# MYBOARD_03-CORE_SRAM.net
KiCad netlist of a schematic drawn in Altium Designer
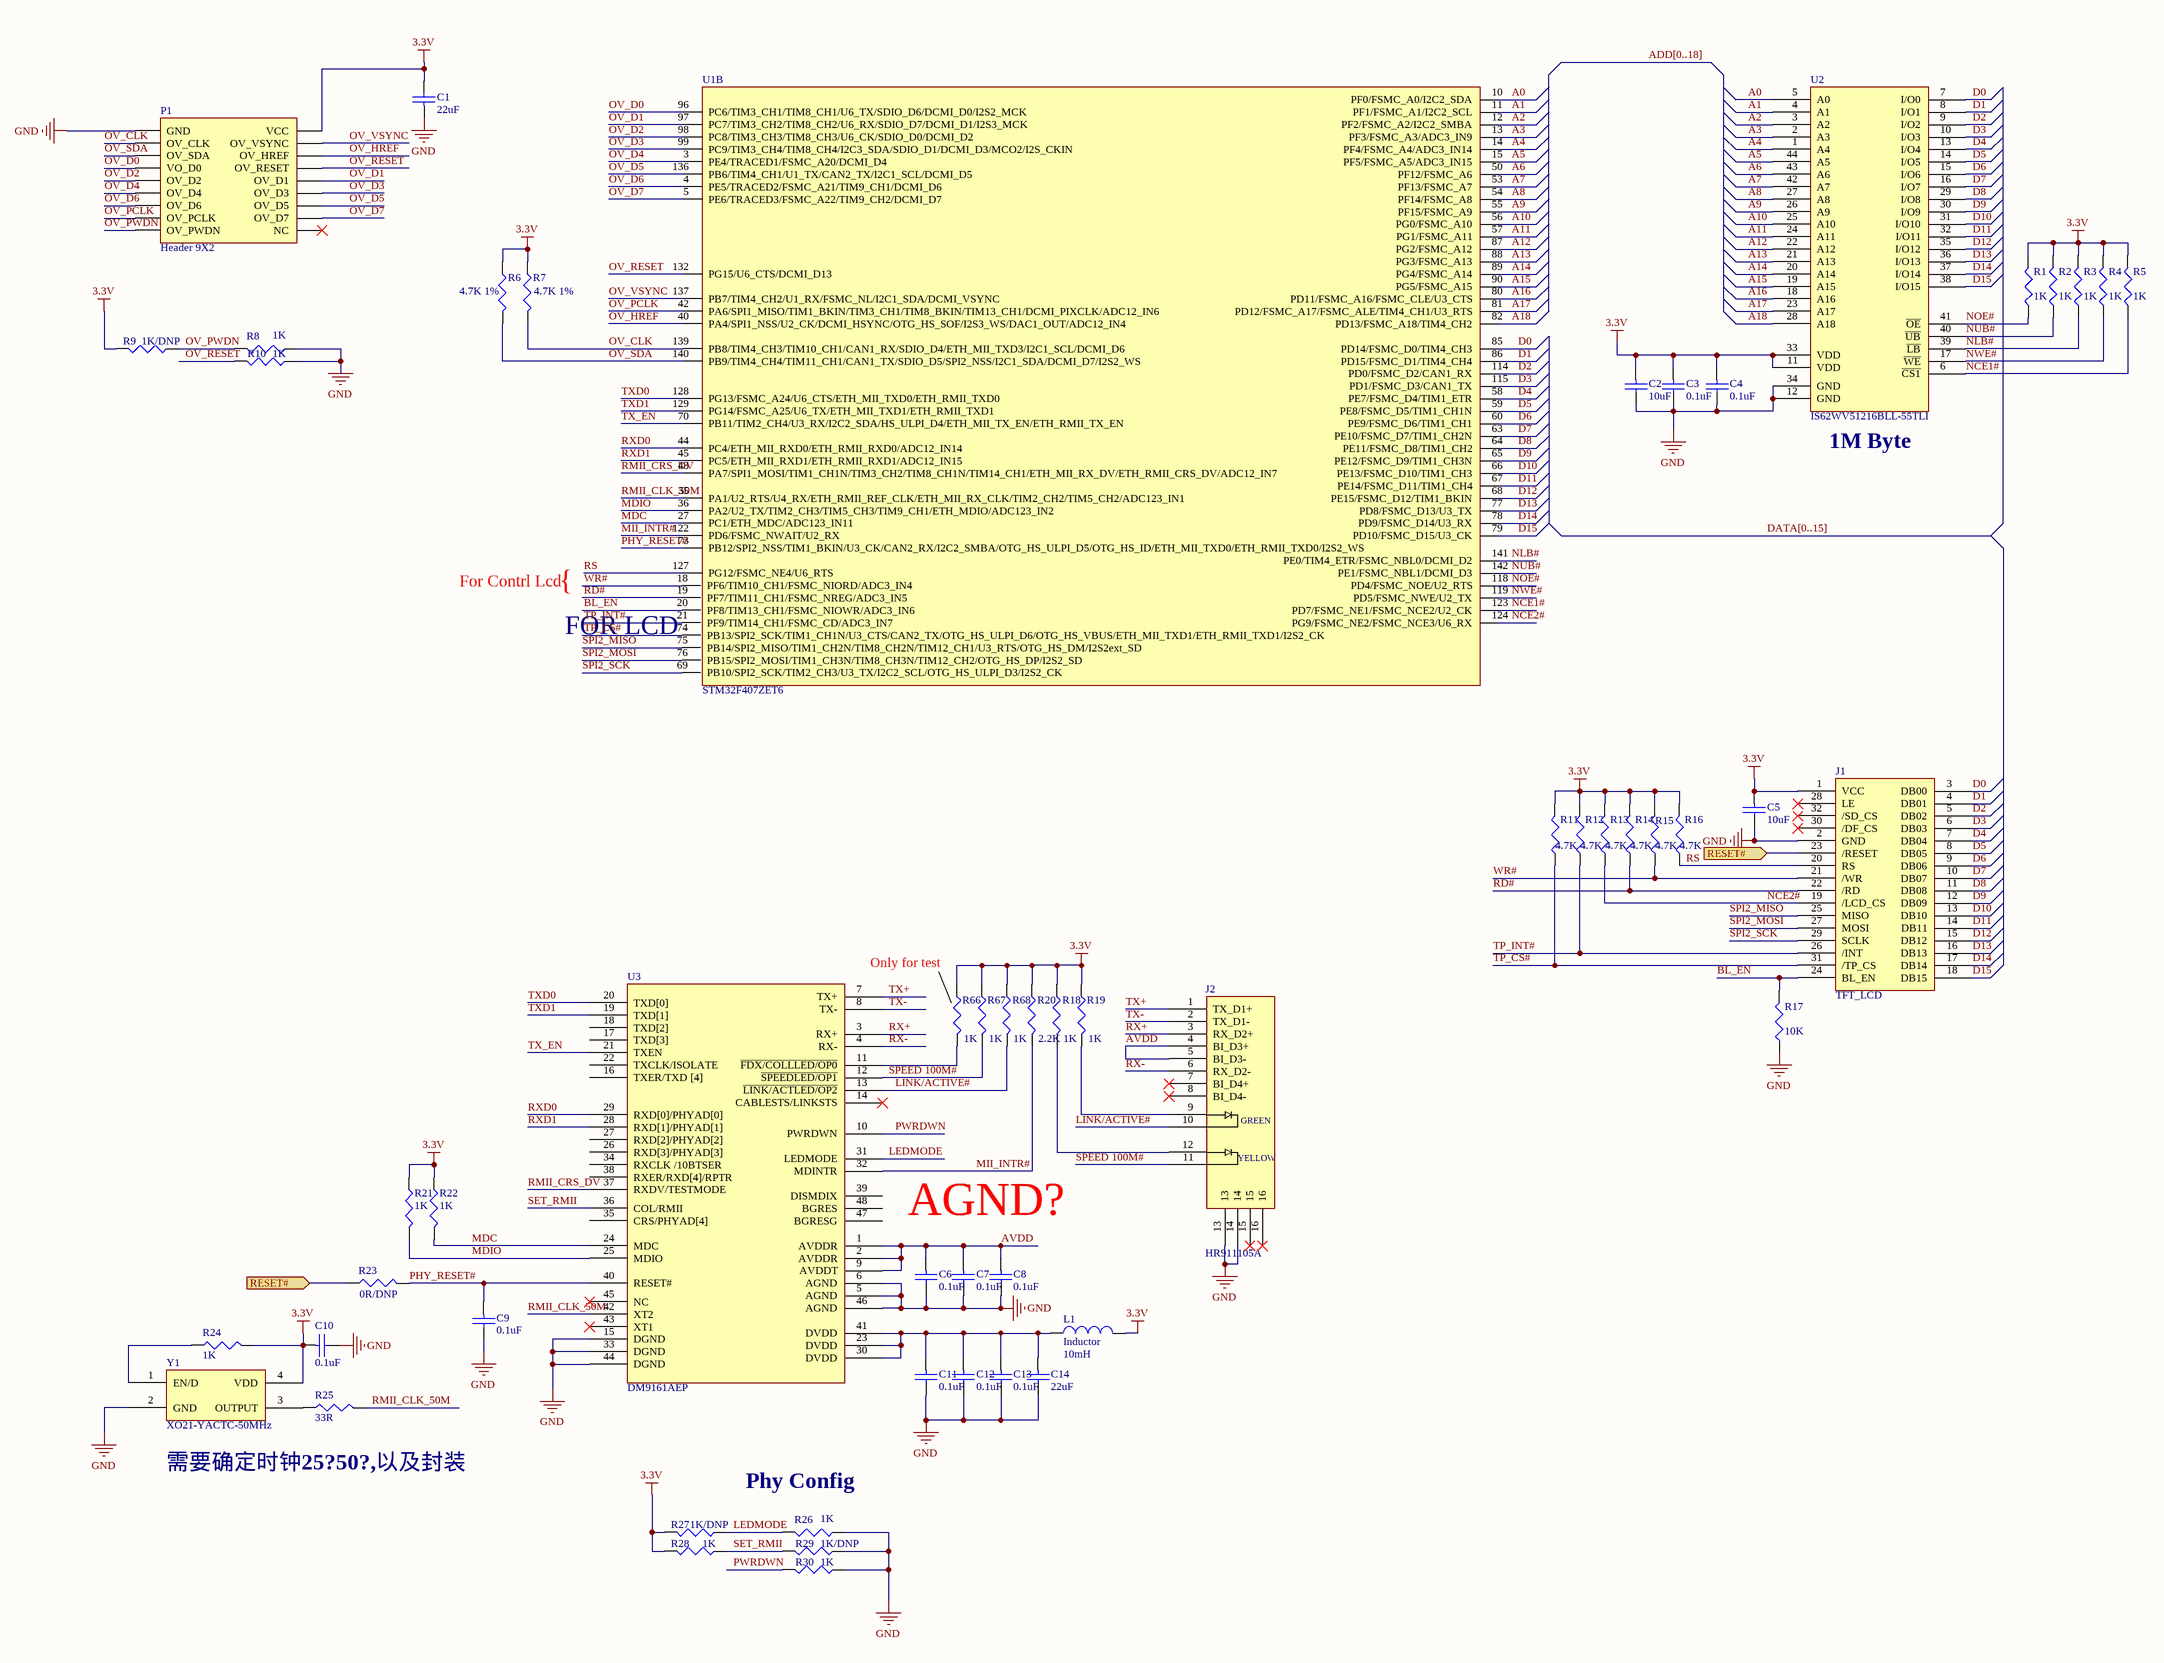
[diagram p0: MYBOARD_03-CORE&SRAM.SchDoc]

(export (version "E")
  (design (tool "Eeschema 10.0.6"))
  (components
    (comp (ref "C1")
      (value "22uF")
      (footprint "C1206")
      (description "Capacitor")
      (libsource (lib "ortho fixture") (part "CAP"))
    )
    (comp (ref "C2")
      (value "10uF")
      (footprint "C0603_DWS")
      (description "Capacitor")
      (libsource (lib "ortho fixture") (part "CAP"))
    )
    (comp (ref "C3")
      (value "0.1uF")
      (footprint "C0603_DWS")
      (description "Capacitor")
      (libsource (lib "ortho fixture") (part "CAP"))
    )
    (comp (ref "C4")
      (value "0.1uF")
      (footprint "C0603_DWS")
      (description "Capacitor")
      (libsource (lib "ortho fixture") (part "CAP"))
    )
    (comp (ref "C5")
      (value "10uF")
      (footprint "C0603_DWS")
      (description "Capacitor")
      (libsource (lib "ortho fixture") (part "CAP"))
    )
    (comp (ref "C6")
      (value "0.1uF")
      (footprint "C0603_DWS")
      (description "Capacitor")
      (libsource (lib "ortho fixture") (part "CAP"))
    )
    (comp (ref "C7")
      (value "0.1uF")
      (footprint "C0603_DWS")
      (description "Capacitor")
      (libsource (lib "ortho fixture") (part "CAP"))
    )
    (comp (ref "C8")
      (value "0.1uF")
      (footprint "C0603_DWS")
      (description "Capacitor")
      (libsource (lib "ortho fixture") (part "CAP"))
    )
    (comp (ref "C9")
      (value "0.1uF")
      (footprint "C0603_DWS")
      (description "Capacitor")
      (libsource (lib "ortho fixture") (part "CAP"))
    )
    (comp (ref "C10")
      (value "0.1uF")
      (footprint "C0603_DWS")
      (description "Capacitor")
      (libsource (lib "ortho fixture") (part "CAP"))
    )
    (comp (ref "C11")
      (value "0.1uF")
      (footprint "C0603_DWS")
      (description "Capacitor")
      (libsource (lib "ortho fixture") (part "CAP"))
    )
    (comp (ref "C12")
      (value "0.1uF")
      (footprint "C0603_DWS")
      (description "Capacitor")
      (libsource (lib "ortho fixture") (part "CAP"))
    )
    (comp (ref "C13")
      (value "0.1uF")
      (footprint "C0603_DWS")
      (description "Capacitor")
      (libsource (lib "ortho fixture") (part "CAP"))
    )
    (comp (ref "C14")
      (value "22uF")
      (footprint "C1206")
      (description "Capacitor")
      (libsource (lib "ortho fixture") (part "CAP"))
    )
    (comp (ref "J1")
      (value "TFT_LCD")
      (footprint "TFT LCD")
      (description "320x240,32PIN,")
      (libsource (lib "ortho fixture") (part "TFT_LCD"))
    )
    (comp (ref "J2")
      (value "HR911105A")
      (footprint "HR911105A")
      (libsource (lib "ortho fixture") (part "RJ45,10/100 Base -TX,有变压器"))
    )
    (comp (ref "L1")
      (value "Inductor")
      (footprint "0603")
      (fields (field (name "ALTIUM_VALUE") "10mH") (field (name "PUBLISHER") "Altium Limited"))
      (libsource (lib "Miscellaneous Devices") (part "Inductor"))
    )
    (comp (ref "P1")
      (value "Header 9X2")
      (footprint "HDR2X9")
      (description "Header, 9-Pin, Dual row")
      (fields (field (name "PUBLISHER") "Altium Limited"))
      (libsource (lib "ortho fixture") (part "Header 9X2"))
    )
    (comp (ref "R1")
      (value "1K")
      (footprint "R0603_5MIL_DWS")
      (description "Resistor")
      (fields (field (name "Comment") "Res3") (field (name "PUBLISHER") "Altium Limited"))
      (libsource (lib "Miscellaneous Devices") (part "Res3"))
    )
    (comp (ref "R2")
      (value "1K")
      (footprint "R0603_5MIL_DWS")
      (description "Resistor")
      (fields (field (name "Comment") "Res3") (field (name "PUBLISHER") "Altium Limited"))
      (libsource (lib "Miscellaneous Devices") (part "Res3"))
    )
    (comp (ref "R3")
      (value "1K")
      (footprint "R0603_5MIL_DWS")
      (description "Resistor")
      (fields (field (name "Comment") "Res3") (field (name "PUBLISHER") "Altium Limited"))
      (libsource (lib "Miscellaneous Devices") (part "Res3"))
    )
    (comp (ref "R4")
      (value "1K")
      (footprint "R0603_5MIL_DWS")
      (description "Resistor")
      (fields (field (name "Comment") "Res3") (field (name "PUBLISHER") "Altium Limited"))
      (libsource (lib "Miscellaneous Devices") (part "Res3"))
    )
    (comp (ref "R5")
      (value "1K")
      (footprint "R0603_5MIL_DWS")
      (description "Resistor")
      (fields (field (name "Comment") "Res3") (field (name "PUBLISHER") "Altium Limited"))
      (libsource (lib "Miscellaneous Devices") (part "Res3"))
    )
    (comp (ref "R6")
      (value "4.7K 1%")
      (footprint "R0603_5MIL_DWS")
      (description "Resistor")
      (fields (field (name "Comment") "Res3") (field (name "PUBLISHER") "Altium Limited"))
      (libsource (lib "Miscellaneous Devices") (part "Res3"))
    )
    (comp (ref "R7")
      (value "4.7K 1%")
      (footprint "R0603_5MIL_DWS")
      (description "Resistor")
      (fields (field (name "Comment") "Res3") (field (name "PUBLISHER") "Altium Limited"))
      (libsource (lib "Miscellaneous Devices") (part "Res3"))
    )
    (comp (ref "R8")
      (value "1K")
      (footprint "R0603_5MIL_DWS")
      (description "Resistor")
      (fields (field (name "Comment") "Res3") (field (name "PUBLISHER") "Altium Limited"))
      (libsource (lib "Miscellaneous Devices") (part "Res3"))
    )
    (comp (ref "R9")
      (value "1K/DNP")
      (footprint "R0603_5MIL_DWS")
      (description "Resistor")
      (fields (field (name "Comment") "Res3") (field (name "PUBLISHER") "Altium Limited"))
      (libsource (lib "Miscellaneous Devices") (part "Res3"))
    )
    (comp (ref "R10")
      (value "1K")
      (footprint "R0603_5MIL_DWS")
      (description "Resistor")
      (fields (field (name "Comment") "Res3") (field (name "PUBLISHER") "Altium Limited"))
      (libsource (lib "Miscellaneous Devices") (part "Res3"))
    )
    (comp (ref "R11")
      (value "4.7K")
      (footprint "R0603_5MIL_DWS")
      (description "Resistor")
      (fields (field (name "Comment") "Res3") (field (name "PUBLISHER") "Altium Limited"))
      (libsource (lib "Miscellaneous Devices") (part "Res3"))
    )
    (comp (ref "R12")
      (value "4.7K")
      (footprint "R0603_5MIL_DWS")
      (description "Resistor")
      (fields (field (name "Comment") "Res3") (field (name "PUBLISHER") "Altium Limited"))
      (libsource (lib "Miscellaneous Devices") (part "Res3"))
    )
    (comp (ref "R13")
      (value "4.7K")
      (footprint "R0603_5MIL_DWS")
      (description "Resistor")
      (fields (field (name "Comment") "Res3") (field (name "PUBLISHER") "Altium Limited"))
      (libsource (lib "Miscellaneous Devices") (part "Res3"))
    )
    (comp (ref "R14")
      (value "4.7K")
      (footprint "R0603_5MIL_DWS")
      (description "Resistor")
      (fields (field (name "Comment") "Res3") (field (name "PUBLISHER") "Altium Limited"))
      (libsource (lib "Miscellaneous Devices") (part "Res3"))
    )
    (comp (ref "R15")
      (value "4.7K")
      (footprint "R0603_5MIL_DWS")
      (description "Resistor")
      (fields (field (name "Comment") "Res3") (field (name "PUBLISHER") "Altium Limited"))
      (libsource (lib "Miscellaneous Devices") (part "Res3"))
    )
    (comp (ref "R16")
      (value "4.7K")
      (footprint "R0603_5MIL_DWS")
      (description "Resistor")
      (fields (field (name "Comment") "Res3") (field (name "PUBLISHER") "Altium Limited"))
      (libsource (lib "Miscellaneous Devices") (part "Res3"))
    )
    (comp (ref "R17")
      (value "10K")
      (footprint "R0603_5MIL_DWS")
      (description "Resistor")
      (fields (field (name "Comment") "Res3") (field (name "PUBLISHER") "Altium Limited"))
      (libsource (lib "Miscellaneous Devices") (part "Res3"))
    )
    (comp (ref "R18")
      (value "1K")
      (footprint "R0603_5MIL_DWS")
      (description "Resistor")
      (fields (field (name "Comment") "Res3") (field (name "PUBLISHER") "Altium Limited"))
      (libsource (lib "Miscellaneous Devices") (part "Res3"))
    )
    (comp (ref "R19")
      (value "1K")
      (footprint "R0603_5MIL_DWS")
      (description "Resistor")
      (fields (field (name "Comment") "Res3") (field (name "PUBLISHER") "Altium Limited"))
      (libsource (lib "Miscellaneous Devices") (part "Res3"))
    )
    (comp (ref "R20")
      (value "2.2K")
      (footprint "R0603_5MIL_DWS")
      (description "Resistor")
      (fields (field (name "Comment") "Res3") (field (name "PUBLISHER") "Altium Limited"))
      (libsource (lib "Miscellaneous Devices") (part "Res3"))
    )
    (comp (ref "R21")
      (value "1K")
      (footprint "R0603_5MIL_DWS")
      (description "Resistor")
      (fields (field (name "Comment") "Res3") (field (name "PUBLISHER") "Altium Limited"))
      (libsource (lib "Miscellaneous Devices") (part "Res3"))
    )
    (comp (ref "R22")
      (value "1K")
      (footprint "R0603_5MIL_DWS")
      (description "Resistor")
      (fields (field (name "Comment") "Res3") (field (name "PUBLISHER") "Altium Limited"))
      (libsource (lib "Miscellaneous Devices") (part "Res3"))
    )
    (comp (ref "R23")
      (value "0R/DNP")
      (footprint "R0603_5MIL_DWS")
      (description "Resistor")
      (fields (field (name "Comment") "Res3") (field (name "PUBLISHER") "Altium Limited"))
      (libsource (lib "Miscellaneous Devices") (part "Res3"))
    )
    (comp (ref "R24")
      (value "1K")
      (footprint "R0603_5MIL_DWS")
      (description "Resistor")
      (fields (field (name "Comment") "Res3") (field (name "PUBLISHER") "Altium Limited"))
      (libsource (lib "Miscellaneous Devices") (part "Res3"))
    )
    (comp (ref "R25")
      (value "33R")
      (footprint "R0603_5MIL_DWS")
      (description "Resistor")
      (fields (field (name "Comment") "Res3") (field (name "PUBLISHER") "Altium Limited"))
      (libsource (lib "Miscellaneous Devices") (part "Res3"))
    )
    (comp (ref "R26")
      (value "1K")
      (footprint "R0603_5MIL_DWS")
      (description "Resistor")
      (fields (field (name "Comment") "Res3") (field (name "PUBLISHER") "Altium Limited"))
      (libsource (lib "Miscellaneous Devices") (part "Res3"))
    )
    (comp (ref "R27")
      (value "1K/DNP")
      (footprint "R0603_5MIL_DWS")
      (description "Resistor")
      (fields (field (name "Comment") "Res3") (field (name "PUBLISHER") "Altium Limited"))
      (libsource (lib "Miscellaneous Devices") (part "Res3"))
    )
    (comp (ref "R28")
      (value "1K")
      (footprint "R0603_5MIL_DWS")
      (description "Resistor")
      (fields (field (name "Comment") "Res3") (field (name "PUBLISHER") "Altium Limited"))
      (libsource (lib "Miscellaneous Devices") (part "Res3"))
    )
    (comp (ref "R29")
      (value "1K/DNP")
      (footprint "R0603_5MIL_DWS")
      (description "Resistor")
      (fields (field (name "Comment") "Res3") (field (name "PUBLISHER") "Altium Limited"))
      (libsource (lib "Miscellaneous Devices") (part "Res3"))
    )
    (comp (ref "R30")
      (value "1K")
      (footprint "R0603_5MIL_DWS")
      (description "Resistor")
      (fields (field (name "Comment") "Res3") (field (name "PUBLISHER") "Altium Limited"))
      (libsource (lib "Miscellaneous Devices") (part "Res3"))
    )
    (comp (ref "R66")
      (value "1K")
      (footprint "R0603_5MIL_DWS")
      (description "Resistor")
      (fields (field (name "Comment") "Res3") (field (name "PUBLISHER") "Altium Limited"))
      (libsource (lib "Miscellaneous Devices") (part "Res3"))
    )
    (comp (ref "R67")
      (value "1K")
      (footprint "R0603_5MIL_DWS")
      (description "Resistor")
      (fields (field (name "Comment") "Res3") (field (name "PUBLISHER") "Altium Limited"))
      (libsource (lib "Miscellaneous Devices") (part "Res3"))
    )
    (comp (ref "R68")
      (value "1K")
      (footprint "R0603_5MIL_DWS")
      (description "Resistor")
      (fields (field (name "Comment") "Res3") (field (name "PUBLISHER") "Altium Limited"))
      (libsource (lib "Miscellaneous Devices") (part "Res3"))
    )
    (comp (ref "U1")
      (value "STM32F407ZET6")
      (footprint "LQFP144")
      (libsource (lib "ortho fixture") (part "STM32F407ZET6"))
    )
    (comp (ref "U2")
      (value "IS62WV51216BLL-55TLI")
      (footprint "TSOP80P1180X120-44N")
      (libsource (lib "ortho fixture") (part "IS62WV51216BLL-55TLI"))
    )
    (comp (ref "U3")
      (value "DM9161AEP")
      (footprint "LQFP-48")
      (libsource (lib "ortho fixture") (part "DM9161AEP"))
    )
    (comp (ref "Y1")
      (value "XO21-YACTC-50MHz")
      (footprint "XO75")
      (description "3.3V,Crystal Oscillator,25M,,Size 2.05×1.65×0.85 mm")
      (libsource (lib "ortho fixture") (part "Oscillator"))
    )
  )
  (nets
    (net (code "36") (name "/A0") (class "Default")
      (node (ref "U1") (pin "10") (pinfunction "PF0/FSMC_A0/I2C2_SDA_10") (pintype "passive"))
      (node (ref "U2") (pin "5") (pinfunction "A0_5") (pintype "passive"))
    )
    (net (code "37") (name "/A1") (class "Default")
      (node (ref "U1") (pin "11") (pinfunction "PF1/FSMC_A1/I2C2_SCL_11") (pintype "passive"))
      (node (ref "U2") (pin "4") (pinfunction "A1_4") (pintype "passive"))
    )
    (net (code "38") (name "/A2") (class "Default")
      (node (ref "U1") (pin "12") (pinfunction "PF2/FSMC_A2/I2C2_SMBA_12") (pintype "passive"))
      (node (ref "U2") (pin "3") (pinfunction "A2_3") (pintype "passive"))
    )
    (net (code "39") (name "/A3") (class "Default")
      (node (ref "U1") (pin "13") (pinfunction "PF3/FSMC_A3/ADC3_IN9_13") (pintype "passive"))
      (node (ref "U2") (pin "2") (pinfunction "A3_2") (pintype "passive"))
    )
    (net (code "40") (name "/A4") (class "Default")
      (node (ref "U1") (pin "14") (pinfunction "PF4/FSMC_A4/ADC3_IN14_14") (pintype "passive"))
      (node (ref "U2") (pin "1") (pinfunction "A4_1") (pintype "passive"))
    )
    (net (code "41") (name "/A5") (class "Default")
      (node (ref "U1") (pin "15") (pinfunction "PF5/FSMC_A5/ADC3_IN15_15") (pintype "passive"))
      (node (ref "U2") (pin "44") (pinfunction "A5_44") (pintype "passive"))
    )
    (net (code "42") (name "/A6") (class "Default")
      (node (ref "U1") (pin "50") (pinfunction "PF12/FSMC_A6_50") (pintype "passive"))
      (node (ref "U2") (pin "43") (pinfunction "A6_43") (pintype "passive"))
    )
    (net (code "43") (name "/A7") (class "Default")
      (node (ref "U1") (pin "53") (pinfunction "PF13/FSMC_A7_53") (pintype "passive"))
      (node (ref "U2") (pin "42") (pinfunction "A7_42") (pintype "passive"))
    )
    (net (code "44") (name "/A8") (class "Default")
      (node (ref "U1") (pin "54") (pinfunction "PF14/FSMC_A8_54") (pintype "passive"))
      (node (ref "U2") (pin "27") (pinfunction "A8_27") (pintype "passive"))
    )
    (net (code "45") (name "/A9") (class "Default")
      (node (ref "U1") (pin "55") (pinfunction "PF15/FSMC_A9_55") (pintype "passive"))
      (node (ref "U2") (pin "26") (pinfunction "A9_26") (pintype "passive"))
    )
    (net (code "46") (name "/A10") (class "Default")
      (node (ref "U1") (pin "56") (pinfunction "PG0/FSMC_A10_56") (pintype "passive"))
      (node (ref "U2") (pin "25") (pinfunction "A10_25") (pintype "passive"))
    )
    (net (code "47") (name "/A11") (class "Default")
      (node (ref "U1") (pin "57") (pinfunction "PG1/FSMC_A11_57") (pintype "passive"))
      (node (ref "U2") (pin "24") (pinfunction "A11_24") (pintype "passive"))
    )
    (net (code "48") (name "/A12") (class "Default")
      (node (ref "U1") (pin "87") (pinfunction "PG2/FSMC_A12_87") (pintype "passive"))
      (node (ref "U2") (pin "22") (pinfunction "A12_22") (pintype "passive"))
    )
    (net (code "49") (name "/A13") (class "Default")
      (node (ref "U1") (pin "88") (pinfunction "PG3/FSMC_A13_88") (pintype "passive"))
      (node (ref "U2") (pin "21") (pinfunction "A13_21") (pintype "passive"))
    )
    (net (code "50") (name "/A14") (class "Default")
      (node (ref "U1") (pin "89") (pinfunction "PG4/FSMC_A14_89") (pintype "passive"))
      (node (ref "U2") (pin "20") (pinfunction "A14_20") (pintype "passive"))
    )
    (net (code "51") (name "/A15") (class "Default")
      (node (ref "U1") (pin "90") (pinfunction "PG5/FSMC_A15_90") (pintype "passive"))
      (node (ref "U2") (pin "19") (pinfunction "A15_19") (pintype "passive"))
    )
    (net (code "52") (name "/A16") (class "Default")
      (node (ref "U1") (pin "80") (pinfunction "PD11/FSMC_A16/FSMC_CLE/U3_CTS_80") (pintype "passive"))
      (node (ref "U2") (pin "18") (pinfunction "A16_18") (pintype "passive"))
    )
    (net (code "53") (name "/A17") (class "Default")
      (node (ref "U1") (pin "81") (pinfunction "PD12/FSMC_A17/FSMC_ALE/TIM4_CH1/U3_RTS_81") (pintype "passive"))
      (node (ref "U2") (pin "23") (pinfunction "A17_23") (pintype "passive"))
    )
    (net (code "54") (name "/A18") (class "Default")
      (node (ref "U1") (pin "82") (pinfunction "PD13/FSMC_A18/TIM4_CH2_82") (pintype "passive"))
      (node (ref "U2") (pin "28") (pinfunction "A18_28") (pintype "passive"))
    )
    (net (code "56") (name "/AVDD") (class "Default")
      (node (ref "C6") (pin "1") (pinfunction "1_1") (pintype "passive"))
      (node (ref "C7") (pin "1") (pinfunction "1_1") (pintype "passive"))
      (node (ref "C8") (pin "1") (pinfunction "1_1") (pintype "passive"))
      (node (ref "J2") (pin "4") (pinfunction "BI_D3+_4") (pintype "passive"))
      (node (ref "J2") (pin "5") (pinfunction "BI_D3-_5") (pintype "passive"))
      (node (ref "U3") (pin "1") (pinfunction "AVDDR_1") (pintype "passive"))
      (node (ref "U3") (pin "2") (pinfunction "AVDDR_2") (pintype "passive"))
      (node (ref "U3") (pin "9") (pinfunction "AVDDT_9") (pintype "passive"))
    )
    (net (code "57") (name "/BL_EN") (class "Default")
      (node (ref "J1") (pin "24") (pinfunction "BL_EN_24") (pintype "passive"))
      (node (ref "R17") (pin "2") (pinfunction "2_2") (pintype "passive"))
      (node (ref "U1") (pin "20") (pinfunction "PF8/TIM13_CH1/FSMC_NIOWR/ADC3_IN6_20") (pintype "passive"))
    )
    (net (code "58") (name "/D0") (class "Default")
      (node (ref "J1") (pin "3") (pinfunction "DB00_3") (pintype "passive"))
      (node (ref "U1") (pin "85") (pinfunction "PD14/FSMC_D0/TIM4_CH3_85") (pintype "passive"))
      (node (ref "U2") (pin "7") (pinfunction "I/O0_7") (pintype "passive"))
    )
    (net (code "59") (name "/D1") (class "Default")
      (node (ref "J1") (pin "4") (pinfunction "DB01_4") (pintype "passive"))
      (node (ref "U1") (pin "86") (pinfunction "PD15/FSMC_D1/TIM4_CH4_86") (pintype "passive"))
      (node (ref "U2") (pin "8") (pinfunction "I/O1_8") (pintype "passive"))
    )
    (net (code "60") (name "/D2") (class "Default")
      (node (ref "J1") (pin "5") (pinfunction "DB02_5") (pintype "passive"))
      (node (ref "U1") (pin "114") (pinfunction "PD0/FSMC_D2/CAN1_RX_114") (pintype "passive"))
      (node (ref "U2") (pin "9") (pinfunction "I/O2_9") (pintype "passive"))
    )
    (net (code "61") (name "/D3") (class "Default")
      (node (ref "J1") (pin "6") (pinfunction "DB03_6") (pintype "passive"))
      (node (ref "U1") (pin "115") (pinfunction "PD1/FSMC_D3/CAN1_TX_115") (pintype "passive"))
      (node (ref "U2") (pin "10") (pinfunction "I/O3_10") (pintype "passive"))
    )
    (net (code "62") (name "/D4") (class "Default")
      (node (ref "J1") (pin "7") (pinfunction "DB04_7") (pintype "passive"))
      (node (ref "U1") (pin "58") (pinfunction "PE7/FSMC_D4/TIM1_ETR_58") (pintype "passive"))
      (node (ref "U2") (pin "13") (pinfunction "I/O4_13") (pintype "passive"))
    )
    (net (code "63") (name "/D5") (class "Default")
      (node (ref "J1") (pin "8") (pinfunction "DB05_8") (pintype "passive"))
      (node (ref "U1") (pin "59") (pinfunction "PE8/FSMC_D5/TIM1_CH1N_59") (pintype "passive"))
      (node (ref "U2") (pin "14") (pinfunction "I/O5_14") (pintype "passive"))
    )
    (net (code "64") (name "/D6") (class "Default")
      (node (ref "J1") (pin "9") (pinfunction "DB06_9") (pintype "passive"))
      (node (ref "U1") (pin "60") (pinfunction "PE9/FSMC_D6/TIM1_CH1_60") (pintype "passive"))
      (node (ref "U2") (pin "15") (pinfunction "I/O6_15") (pintype "passive"))
    )
    (net (code "65") (name "/D7") (class "Default")
      (node (ref "J1") (pin "10") (pinfunction "DB07_10") (pintype "passive"))
      (node (ref "U1") (pin "63") (pinfunction "PE10/FSMC_D7/TIM1_CH2N_63") (pintype "passive"))
      (node (ref "U2") (pin "16") (pinfunction "I/O7_16") (pintype "passive"))
    )
    (net (code "66") (name "/D8") (class "Default")
      (node (ref "J1") (pin "11") (pinfunction "DB08_11") (pintype "passive"))
      (node (ref "U1") (pin "64") (pinfunction "PE11/FSMC_D8/TIM1_CH2_64") (pintype "passive"))
      (node (ref "U2") (pin "29") (pinfunction "I/O8_29") (pintype "passive"))
    )
    (net (code "67") (name "/D9") (class "Default")
      (node (ref "J1") (pin "12") (pinfunction "DB09_12") (pintype "passive"))
      (node (ref "U1") (pin "65") (pinfunction "PE12/FSMC_D9/TIM1_CH3N_65") (pintype "passive"))
      (node (ref "U2") (pin "30") (pinfunction "I/O9_30") (pintype "passive"))
    )
    (net (code "68") (name "/D10") (class "Default")
      (node (ref "J1") (pin "13") (pinfunction "DB10_13") (pintype "passive"))
      (node (ref "U1") (pin "66") (pinfunction "PE13/FSMC_D10/TIM1_CH3_66") (pintype "passive"))
      (node (ref "U2") (pin "31") (pinfunction "I/O10_31") (pintype "passive"))
    )
    (net (code "69") (name "/D11") (class "Default")
      (node (ref "J1") (pin "14") (pinfunction "DB11_14") (pintype "passive"))
      (node (ref "U1") (pin "67") (pinfunction "PE14/FSMC_D11/TIM1_CH4_67") (pintype "passive"))
      (node (ref "U2") (pin "32") (pinfunction "I/O11_32") (pintype "passive"))
    )
    (net (code "70") (name "/D12") (class "Default")
      (node (ref "J1") (pin "15") (pinfunction "DB12_15") (pintype "passive"))
      (node (ref "U1") (pin "68") (pinfunction "PE15/FSMC_D12/TIM1_BKIN_68") (pintype "passive"))
      (node (ref "U2") (pin "35") (pinfunction "I/O12_35") (pintype "passive"))
    )
    (net (code "71") (name "/D13") (class "Default")
      (node (ref "J1") (pin "16") (pinfunction "DB13_16") (pintype "passive"))
      (node (ref "U1") (pin "77") (pinfunction "PD8/FSMC_D13/U3_TX_77") (pintype "passive"))
      (node (ref "U2") (pin "36") (pinfunction "I/O13_36") (pintype "passive"))
    )
    (net (code "72") (name "/D14") (class "Default")
      (node (ref "J1") (pin "17") (pinfunction "DB14_17") (pintype "passive"))
      (node (ref "U1") (pin "78") (pinfunction "PD9/FSMC_D14/U3_RX_78") (pintype "passive"))
      (node (ref "U2") (pin "37") (pinfunction "I/O14_37") (pintype "passive"))
    )
    (net (code "73") (name "/D15") (class "Default")
      (node (ref "J1") (pin "18") (pinfunction "DB15_18") (pintype "passive"))
      (node (ref "U1") (pin "79") (pinfunction "PD10/FSMC_D15/U3_CK_79") (pintype "passive"))
      (node (ref "U2") (pin "38") (pinfunction "I/O15_38") (pintype "passive"))
    )
    (net (code "75") (name "/LEDMODE") (class "Default")
      (node (ref "R26") (pin "2") (pinfunction "2_2") (pintype "passive"))
      (node (ref "R27") (pin "1") (pinfunction "1_1") (pintype "passive"))
      (node (ref "U3") (pin "31") (pinfunction "LEDMODE_31") (pintype "passive"))
    )
    (net (code "76") (name "/LINK{slash}ACTIVE#") (class "Default")
      (node (ref "J2") (pin "10") (pinfunction "10_10") (pintype "passive"))
      (node (ref "R68") (pin "2") (pinfunction "2_2") (pintype "passive"))
      (node (ref "U3") (pin "13") (pinfunction "~{LINK/ACTLED/OP2}_13") (pintype "passive"))
    )
    (net (code "77") (name "/MDC") (class "Default")
      (node (ref "R22") (pin "2") (pinfunction "2_2") (pintype "passive"))
      (node (ref "U1") (pin "27") (pinfunction "PC1/ETH_MDC/ADC123_IN11_27") (pintype "passive"))
      (node (ref "U3") (pin "24") (pinfunction "MDC_24") (pintype "passive"))
    )
    (net (code "78") (name "/MDIO") (class "Default")
      (node (ref "R21") (pin "2") (pinfunction "2_2") (pintype "passive"))
      (node (ref "U1") (pin "36") (pinfunction "PA2/U2_TX/TIM2_CH3/TIM5_CH3/TIM9_CH1/ETH_MDIO/ADC123_IN2_36") (pintype "passive"))
      (node (ref "U3") (pin "25") (pinfunction "MDIO_25") (pintype "passive"))
    )
    (net (code "79") (name "/MII_INTR#") (class "Default")
      (node (ref "R20") (pin "2") (pinfunction "2_2") (pintype "passive"))
      (node (ref "U1") (pin "122") (pinfunction "PD6/FSMC_NWAIT/U2_RX_122") (pintype "passive"))
      (node (ref "U3") (pin "32") (pinfunction "MDINTR_32") (pintype "passive"))
    )
    (net (code "80") (name "/NCE1#") (class "Default")
      (node (ref "R5") (pin "1") (pinfunction "1_1") (pintype "passive"))
      (node (ref "U1") (pin "123") (pinfunction "PD7/FSMC_NE1/FSMC_NCE2/U2_CK_123") (pintype "passive"))
      (node (ref "U2") (pin "6") (pinfunction "~{CS1}_6") (pintype "passive"))
    )
    (net (code "81") (name "/NCE2#") (class "Default")
      (node (ref "J1") (pin "19") (pinfunction "/LCD_CS_19") (pintype "passive"))
      (node (ref "R13") (pin "1") (pinfunction "1_1") (pintype "passive"))
      (node (ref "U1") (pin "124") (pinfunction "PG9/FSMC_NE2/FSMC_NCE3/U6_RX_124") (pintype "passive"))
    )
    (net (code "82") (name "/NLB#") (class "Default")
      (node (ref "R3") (pin "1") (pinfunction "1_1") (pintype "passive"))
      (node (ref "U1") (pin "141") (pinfunction "PE0/TIM4_ETR/FSMC_NBL0/DCMI_D2_141") (pintype "passive"))
      (node (ref "U2") (pin "39") (pinfunction "~{LB}_39") (pintype "passive"))
    )
    (net (code "83") (name "/NOE#") (class "Default")
      (node (ref "R1") (pin "1") (pinfunction "1_1") (pintype "passive"))
      (node (ref "U1") (pin "118") (pinfunction "PD4/FSMC_NOE/U2_RTS_118") (pintype "passive"))
      (node (ref "U2") (pin "41") (pinfunction "~{OE}_41") (pintype "passive"))
    )
    (net (code "84") (name "/NUB#") (class "Default")
      (node (ref "R2") (pin "1") (pinfunction "1_1") (pintype "passive"))
      (node (ref "U1") (pin "142") (pinfunction "PE1/FSMC_NBL1/DCMI_D3_142") (pintype "passive"))
      (node (ref "U2") (pin "40") (pinfunction "~{UB}_40") (pintype "passive"))
    )
    (net (code "85") (name "/NWE#") (class "Default")
      (node (ref "R4") (pin "1") (pinfunction "1_1") (pintype "passive"))
      (node (ref "U1") (pin "119") (pinfunction "PD5/FSMC_NWE/U2_TX_119") (pintype "passive"))
      (node (ref "U2") (pin "17") (pinfunction "~{WE}_17") (pintype "passive"))
    )
    (net (code "86") (name "/OV_CLK") (class "Default")
      (node (ref "P1") (pin "3") (pinfunction "OV_CLK_3") (pintype "passive"))
      (node (ref "R7") (pin "2") (pinfunction "2_2") (pintype "passive"))
      (node (ref "U1") (pin "139") (pinfunction "PB8/TIM4_CH3/TIM10_CH1/CAN1_RX/SDIO_D4/ETH_MII_TXD3/I2C1_SCL/DCMI_D6_139") (pintype "passive"))
    )
    (net (code "87") (name "/OV_D0") (class "Default")
      (node (ref "P1") (pin "7") (pinfunction "VO_D0_7") (pintype "passive"))
      (node (ref "U1") (pin "96") (pinfunction "PC6/TIM3_CH1/TIM8_CH1/U6_TX/SDIO_D6/DCMI_D0/I2S2_MCK_96") (pintype "passive"))
    )
    (net (code "88") (name "/OV_D1") (class "Default")
      (node (ref "P1") (pin "10") (pinfunction "OV_D1_10") (pintype "passive"))
      (node (ref "U1") (pin "97") (pinfunction "PC7/TIM3_CH2/TIM8_CH2/U6_RX/SDIO_D7/DCMI_D1/I2S3_MCK_97") (pintype "passive"))
    )
    (net (code "89") (name "/OV_D2") (class "Default")
      (node (ref "P1") (pin "9") (pinfunction "OV_D2_9") (pintype "passive"))
      (node (ref "U1") (pin "98") (pinfunction "PC8/TIM3_CH3/TIM8_CH3/U6_CK/SDIO_D0/DCMI_D2_98") (pintype "passive"))
    )
    (net (code "90") (name "/OV_D3") (class "Default")
      (node (ref "P1") (pin "12") (pinfunction "OV_D3_12") (pintype "passive"))
      (node (ref "U1") (pin "99") (pinfunction "PC9/TIM3_CH4/TIM8_CH4/I2C3_SDA/SDIO_D1/DCMI_D3/MCO2/I2S_CKIN_99") (pintype "passive"))
    )
    (net (code "91") (name "/OV_D4") (class "Default")
      (node (ref "P1") (pin "11") (pinfunction "OV_D4_11") (pintype "passive"))
      (node (ref "U1") (pin "3") (pinfunction "PE4/TRACED1/FSMC_A20/DCMI_D4_3") (pintype "passive"))
    )
    (net (code "92") (name "/OV_D5") (class "Default")
      (node (ref "P1") (pin "14") (pinfunction "OV_D5_14") (pintype "passive"))
      (node (ref "U1") (pin "136") (pinfunction "PB6/TIM4_CH1/U1_TX/CAN2_TX/I2C1_SCL/DCMI_D5_136") (pintype "passive"))
    )
    (net (code "93") (name "/OV_D6") (class "Default")
      (node (ref "P1") (pin "13") (pinfunction "OV_D6_13") (pintype "passive"))
      (node (ref "U1") (pin "4") (pinfunction "PE5/TRACED2/FSMC_A21/TIM9_CH1/DCMI_D6_4") (pintype "passive"))
    )
    (net (code "94") (name "/OV_D7") (class "Default")
      (node (ref "P1") (pin "16") (pinfunction "OV_D7_16") (pintype "passive"))
      (node (ref "U1") (pin "5") (pinfunction "PE6/TRACED3/FSMC_A22/TIM9_CH2/DCMI_D7_5") (pintype "passive"))
    )
    (net (code "95") (name "/OV_HREF") (class "Default")
      (node (ref "P1") (pin "6") (pinfunction "OV_HREF_6") (pintype "passive"))
      (node (ref "U1") (pin "40") (pinfunction "PA4/SPI1_NSS/U2_CK/DCMI_HSYNC/OTG_HS_SOF/I2S3_WS/DAC1_OUT/ADC12_IN4_40") (pintype "passive"))
    )
    (net (code "96") (name "/OV_PCLK") (class "Default")
      (node (ref "P1") (pin "15") (pinfunction "OV_PCLK_15") (pintype "passive"))
      (node (ref "U1") (pin "42") (pinfunction "PA6/SPI1_MISO/TIM1_BKIN/TIM3_CH1/TIM8_BKIN/TIM13_CH1/DCMI_PIXCLK/ADC12_IN6_42") (pintype "passive"))
    )
    (net (code "97") (name "/OV_PWDN") (class "Default")
      (node (ref "P1") (pin "17") (pinfunction "OV_PWDN_17") (pintype "passive"))
      (node (ref "R8") (pin "2") (pinfunction "2_2") (pintype "passive"))
      (node (ref "R9") (pin "1") (pinfunction "1_1") (pintype "passive"))
    )
    (net (code "98") (name "/OV_RESET") (class "Default")
      (node (ref "P1") (pin "8") (pinfunction "OV_RESET_8") (pintype "passive"))
      (node (ref "R10") (pin "2") (pinfunction "2_2") (pintype "passive"))
      (node (ref "U1") (pin "132") (pinfunction "PG15/U6_CTS/DCMI_D13_132") (pintype "passive"))
    )
    (net (code "99") (name "/OV_SDA") (class "Default")
      (node (ref "P1") (pin "5") (pinfunction "OV_SDA_5") (pintype "passive"))
      (node (ref "R6") (pin "2") (pinfunction "2_2") (pintype "passive"))
      (node (ref "U1") (pin "140") (pinfunction "PB9/TIM4_CH4/TIM11_CH1/CAN1_TX/SDIO_D5/SPI2_NSS/I2C1_SDA/DCMI_D7/I2S2_WS_140") (pintype "passive"))
    )
    (net (code "100") (name "/OV_VSYNC") (class "Default")
      (node (ref "P1") (pin "4") (pinfunction "OV_VSYNC_4") (pintype "passive"))
      (node (ref "U1") (pin "137") (pinfunction "PB7/TIM4_CH2/U1_RX/FSMC_NL/I2C1_SDA/DCMI_VSYNC_137") (pintype "passive"))
    )
    (net (code "101") (name "/PHY_RESET#") (class "Default")
      (node (ref "C9") (pin "1") (pinfunction "1_1") (pintype "passive"))
      (node (ref "R23") (pin "2") (pinfunction "2_2") (pintype "passive"))
      (node (ref "U1") (pin "73") (pinfunction "PB12/SPI2_NSS/TIM1_BKIN/U3_CK/CAN2_RX/I2C2_SMBA/OTG_HS_ULPI_D5/OTG_HS_ID/ETH_MII_TXD0/ETH_RMII_TXD0/I2S2_WS_73") (pintype "passive"))
      (node (ref "U3") (pin "40") (pinfunction "RESET#_40") (pintype "passive"))
    )
    (net (code "102") (name "/PWRDWN") (class "Default")
      (node (ref "R30") (pin "2") (pinfunction "2_2") (pintype "passive"))
      (node (ref "U3") (pin "10") (pinfunction "PWRDWN_10") (pintype "passive"))
    )
    (net (code "103") (name "/RD#") (class "Default")
      (node (ref "J1") (pin "22") (pinfunction "/RD_22") (pintype "passive"))
      (node (ref "R14") (pin "1") (pinfunction "1_1") (pintype "passive"))
      (node (ref "U1") (pin "19") (pinfunction "PF7/TIM11_CH1/FSMC_NREG/ADC3_IN5_19") (pintype "passive"))
    )
    (net (code "104") (name "/RESET#") (class "Default")
      (node (ref "J1") (pin "23") (pinfunction "/RESET_23") (pintype "passive"))
      (node (ref "R23") (pin "1") (pinfunction "1_1") (pintype "passive"))
    )
    (net (code "105") (name "/RMII_CLK_50M") (class "Default")
      (node (ref "R25") (pin "2") (pinfunction "2_2") (pintype "passive"))
      (node (ref "U1") (pin "35") (pinfunction "PA1/U2_RTS/U4_RX/ETH_RMII_REF_CLK/ETH_MII_RX_CLK/TIM2_CH2/TIM5_CH2/ADC123_IN1_35") (pintype "passive"))
      (node (ref "U3") (pin "42") (pinfunction "XT2_42") (pintype "passive"))
    )
    (net (code "106") (name "/RMII_CRS_DV") (class "Default")
      (node (ref "U1") (pin "43") (pinfunction "PA7/SPI1_MOSI/TIM1_CH1N/TIM3_CH2/TIM8_CH1N/TIM14_CH1/ETH_MII_RX_DV/ETH_RMII_CRS_DV/ADC12_IN7_43") (pintype "passive"))
      (node (ref "U3") (pin "37") (pinfunction "RXDV/TESTMODE_37") (pintype "passive"))
    )
    (net (code "107") (name "/RS") (class "Default")
      (node (ref "J1") (pin "20") (pinfunction "RS_20") (pintype "passive"))
      (node (ref "R16") (pin "1") (pinfunction "1_1") (pintype "passive"))
      (node (ref "U1") (pin "127") (pinfunction "PG12/FSMC_NE4/U6_RTS_127") (pintype "passive"))
    )
    (net (code "108") (name "/RX+") (class "Default")
      (node (ref "J2") (pin "3") (pinfunction "RX_D2+_3") (pintype "passive"))
      (node (ref "U3") (pin "3") (pinfunction "RX+_3") (pintype "passive"))
    )
    (net (code "109") (name "/RX-") (class "Default")
      (node (ref "J2") (pin "6") (pinfunction "RX_D2-_6") (pintype "passive"))
      (node (ref "U3") (pin "4") (pinfunction "RX-_4") (pintype "passive"))
    )
    (net (code "110") (name "/RXD0") (class "Default")
      (node (ref "U1") (pin "44") (pinfunction "PC4/ETH_MII_RXD0/ETH_RMII_RXD0/ADC12_IN14_44") (pintype "passive"))
      (node (ref "U3") (pin "29") (pinfunction "RXD[0]/PHYAD[0]_29") (pintype "passive"))
    )
    (net (code "111") (name "/RXD1") (class "Default")
      (node (ref "U1") (pin "45") (pinfunction "PC5/ETH_MII_RXD1/ETH_RMII_RXD1/ADC12_IN15_45") (pintype "passive"))
      (node (ref "U3") (pin "28") (pinfunction "RXD[1]/PHYAD[1]_28") (pintype "passive"))
    )
    (net (code "112") (name "/SET_RMII") (class "Default")
      (node (ref "R28") (pin "1") (pinfunction "1_1") (pintype "passive"))
      (node (ref "R29") (pin "2") (pinfunction "2_2") (pintype "passive"))
      (node (ref "U3") (pin "36") (pinfunction "COL/RMII_36") (pintype "passive"))
    )
    (net (code "113") (name "/SPEED 100M#") (class "Default")
      (node (ref "J2") (pin "11") (pinfunction "11_11") (pintype "passive"))
      (node (ref "R67") (pin "2") (pinfunction "2_2") (pintype "passive"))
      (node (ref "U3") (pin "12") (pinfunction "~{SPEEDLED/OP1}_12") (pintype "passive"))
    )
    (net (code "114") (name "/SPI2_MISO") (class "Default")
      (node (ref "J1") (pin "25") (pinfunction "MISO_25") (pintype "passive"))
      (node (ref "U1") (pin "75") (pinfunction "PB14/SPI2_MISO/TIM1_CH2N/TIM8_CH2N/TIM12_CH1/U3_RTS/OTG_HS_DM/I2S2ext_SD_75") (pintype "passive"))
    )
    (net (code "115") (name "/SPI2_MOSI") (class "Default")
      (node (ref "J1") (pin "27") (pinfunction "MOSI_27") (pintype "passive"))
      (node (ref "U1") (pin "76") (pinfunction "PB15/SPI2_MOSI/TIM1_CH3N/TIM8_CH3N/TIM12_CH2/OTG_HS_DP/I2S2_SD_76") (pintype "passive"))
    )
    (net (code "116") (name "/SPI2_SCK") (class "Default")
      (node (ref "J1") (pin "29") (pinfunction "SCLK_29") (pintype "passive"))
      (node (ref "U1") (pin "69") (pinfunction "PB10/SPI2_SCK/TIM2_CH3/U3_TX/I2C2_SCL/OTG_HS_ULPI_D3/I2S2_CK_69") (pintype "passive"))
    )
    (net (code "117") (name "/TP_CS#") (class "Default")
      (node (ref "J1") (pin "31") (pinfunction "/TP_CS_31") (pintype "passive"))
      (node (ref "R11") (pin "1") (pinfunction "1_1") (pintype "passive"))
      (node (ref "U1") (pin "74") (pinfunction "PB13/SPI2_SCK/TIM1_CH1N/U3_CTS/CAN2_TX/OTG_HS_ULPI_D6/OTG_HS_VBUS/ETH_MII_TXD1/ETH_RMII_TXD1/I2S2_CK_74") (pintype "passive"))
    )
    (net (code "118") (name "/TP_INT#") (class "Default")
      (node (ref "J1") (pin "26") (pinfunction "/INT_26") (pintype "passive"))
      (node (ref "R12") (pin "1") (pinfunction "1_1") (pintype "passive"))
      (node (ref "U1") (pin "21") (pinfunction "PF9/TIM14_CH1/FSMC_CD/ADC3_IN7_21") (pintype "passive"))
    )
    (net (code "119") (name "/TX+") (class "Default")
      (node (ref "J2") (pin "1") (pinfunction "TX_D1+_1") (pintype "passive"))
      (node (ref "U3") (pin "7") (pinfunction "TX+_7") (pintype "passive"))
    )
    (net (code "120") (name "/TX-") (class "Default")
      (node (ref "J2") (pin "2") (pinfunction "TX_D1-_2") (pintype "passive"))
      (node (ref "U3") (pin "8") (pinfunction "TX-_8") (pintype "passive"))
    )
    (net (code "121") (name "/TXD0") (class "Default")
      (node (ref "U1") (pin "128") (pinfunction "PG13/FSMC_A24/U6_CTS/ETH_MII_TXD0/ETH_RMII_TXD0_128") (pintype "passive"))
      (node (ref "U3") (pin "20") (pinfunction "TXD[0]_20") (pintype "passive"))
    )
    (net (code "122") (name "/TXD1") (class "Default")
      (node (ref "U1") (pin "129") (pinfunction "PG14/FSMC_A25/U6_TX/ETH_MII_TXD1/ETH_RMII_TXD1_129") (pintype "passive"))
      (node (ref "U3") (pin "19") (pinfunction "TXD[1]_19") (pintype "passive"))
    )
    (net (code "123") (name "/TX_EN") (class "Default")
      (node (ref "U1") (pin "70") (pinfunction "PB11/TIM2_CH4/U3_RX/I2C2_SDA/HS_ULPI_D4/ETH_MII_TX_EN/ETH_RMII_TX_EN_70") (pintype "passive"))
      (node (ref "U3") (pin "21") (pinfunction "TXEN_21") (pintype "passive"))
    )
    (net (code "124") (name "/WR#") (class "Default")
      (node (ref "J1") (pin "21") (pinfunction "/WR_21") (pintype "passive"))
      (node (ref "R15") (pin "1") (pinfunction "1_1") (pintype "passive"))
      (node (ref "U1") (pin "18") (pinfunction "PF6/TIM10_CH1/FSMC_NIORD/ADC3_IN4_18") (pintype "passive"))
    )
    (net (code "125") (name "3.3V") (class "Default")
      (node (ref "C1") (pin "2") (pinfunction "2_2") (pintype "passive"))
      (node (ref "C10") (pin "1") (pinfunction "1_1") (pintype "passive"))
      (node (ref "C2") (pin "1") (pinfunction "1_1") (pintype "passive"))
      (node (ref "C3") (pin "1") (pinfunction "1_1") (pintype "passive"))
      (node (ref "C4") (pin "1") (pinfunction "1_1") (pintype "passive"))
      (node (ref "C5") (pin "1") (pinfunction "1_1") (pintype "passive"))
      (node (ref "J1") (pin "1") (pinfunction "VCC_1") (pintype "passive"))
      (node (ref "L1") (pin "2") (pinfunction "2_2") (pintype "passive"))
      (node (ref "P1") (pin "2") (pinfunction "VCC_2") (pintype "passive"))
      (node (ref "R1") (pin "2") (pinfunction "2_2") (pintype "passive"))
      (node (ref "R11") (pin "2") (pinfunction "2_2") (pintype "passive"))
      (node (ref "R12") (pin "2") (pinfunction "2_2") (pintype "passive"))
      (node (ref "R13") (pin "2") (pinfunction "2_2") (pintype "passive"))
      (node (ref "R14") (pin "2") (pinfunction "2_2") (pintype "passive"))
      (node (ref "R15") (pin "2") (pinfunction "2_2") (pintype "passive"))
      (node (ref "R16") (pin "2") (pinfunction "2_2") (pintype "passive"))
      (node (ref "R18") (pin "1") (pinfunction "1_1") (pintype "passive"))
      (node (ref "R19") (pin "1") (pinfunction "1_1") (pintype "passive"))
      (node (ref "R2") (pin "2") (pinfunction "2_2") (pintype "passive"))
      (node (ref "R20") (pin "1") (pinfunction "1_1") (pintype "passive"))
      (node (ref "R21") (pin "1") (pinfunction "1_1") (pintype "passive"))
      (node (ref "R22") (pin "1") (pinfunction "1_1") (pintype "passive"))
      (node (ref "R24") (pin "2") (pinfunction "2_2") (pintype "passive"))
      (node (ref "R27") (pin "2") (pinfunction "2_2") (pintype "passive"))
      (node (ref "R28") (pin "2") (pinfunction "2_2") (pintype "passive"))
      (node (ref "R3") (pin "2") (pinfunction "2_2") (pintype "passive"))
      (node (ref "R4") (pin "2") (pinfunction "2_2") (pintype "passive"))
      (node (ref "R5") (pin "2") (pinfunction "2_2") (pintype "passive"))
      (node (ref "R6") (pin "1") (pinfunction "1_1") (pintype "passive"))
      (node (ref "R66") (pin "1") (pinfunction "1_1") (pintype "passive"))
      (node (ref "R67") (pin "1") (pinfunction "1_1") (pintype "passive"))
      (node (ref "R68") (pin "1") (pinfunction "1_1") (pintype "passive"))
      (node (ref "R7") (pin "1") (pinfunction "1_1") (pintype "passive"))
      (node (ref "R9") (pin "2") (pinfunction "2_2") (pintype "passive"))
      (node (ref "U2") (pin "11") (pinfunction "VDD_11") (pintype "passive"))
      (node (ref "U2") (pin "33") (pinfunction "VDD_33") (pintype "passive"))
      (node (ref "Y1") (pin "4") (pinfunction "VDD_4") (pintype "power_in"))
    )
    (net (code "126") (name "GND") (class "Default")
      (node (ref "C1") (pin "1") (pinfunction "1_1") (pintype "passive"))
      (node (ref "C10") (pin "2") (pinfunction "2_2") (pintype "passive"))
      (node (ref "C11") (pin "2") (pinfunction "2_2") (pintype "passive"))
      (node (ref "C12") (pin "2") (pinfunction "2_2") (pintype "passive"))
      (node (ref "C13") (pin "2") (pinfunction "2_2") (pintype "passive"))
      (node (ref "C14") (pin "2") (pinfunction "2_2") (pintype "passive"))
      (node (ref "C2") (pin "2") (pinfunction "2_2") (pintype "passive"))
      (node (ref "C3") (pin "2") (pinfunction "2_2") (pintype "passive"))
      (node (ref "C4") (pin "2") (pinfunction "2_2") (pintype "passive"))
      (node (ref "C5") (pin "2") (pinfunction "2_2") (pintype "passive"))
      (node (ref "C6") (pin "2") (pinfunction "2_2") (pintype "passive"))
      (node (ref "C7") (pin "2") (pinfunction "2_2") (pintype "passive"))
      (node (ref "C8") (pin "2") (pinfunction "2_2") (pintype "passive"))
      (node (ref "C9") (pin "2") (pinfunction "2_2") (pintype "passive"))
      (node (ref "J1") (pin "2") (pinfunction "GND_2") (pintype "passive"))
      (node (ref "J2") (pin "13") (pinfunction "13_13") (pintype "passive"))
      (node (ref "J2") (pin "14") (pinfunction "14_14") (pintype "passive"))
      (node (ref "P1") (pin "1") (pinfunction "GND_1") (pintype "passive"))
      (node (ref "R10") (pin "1") (pinfunction "1_1") (pintype "passive"))
      (node (ref "R17") (pin "1") (pinfunction "1_1") (pintype "passive"))
      (node (ref "R26") (pin "1") (pinfunction "1_1") (pintype "passive"))
      (node (ref "R29") (pin "1") (pinfunction "1_1") (pintype "passive"))
      (node (ref "R30") (pin "1") (pinfunction "1_1") (pintype "passive"))
      (node (ref "R8") (pin "1") (pinfunction "1_1") (pintype "passive"))
      (node (ref "U2") (pin "12") (pinfunction "GND_12") (pintype "passive"))
      (node (ref "U2") (pin "34") (pinfunction "GND_34") (pintype "passive"))
      (node (ref "U3") (pin "15") (pinfunction "DGND_15") (pintype "passive"))
      (node (ref "U3") (pin "33") (pinfunction "DGND_33") (pintype "passive"))
      (node (ref "U3") (pin "44") (pinfunction "DGND_44") (pintype "passive"))
      (node (ref "U3") (pin "46") (pinfunction "AGND_46") (pintype "passive"))
      (node (ref "U3") (pin "5") (pinfunction "AGND_5") (pintype "passive"))
      (node (ref "U3") (pin "6") (pinfunction "AGND_6") (pintype "passive"))
      (node (ref "Y1") (pin "2") (pinfunction "GND_2") (pintype "power_in"))
    )
    (net (code "127") (name "Net-(C11-Pad1)") (class "Default")
      (node (ref "C11") (pin "1") (pinfunction "1_1") (pintype "passive"))
      (node (ref "C12") (pin "1") (pinfunction "1_1") (pintype "passive"))
      (node (ref "C13") (pin "1") (pinfunction "1_1") (pintype "passive"))
      (node (ref "C14") (pin "1") (pinfunction "1_1") (pintype "passive"))
      (node (ref "L1") (pin "1") (pinfunction "1_1") (pintype "passive"))
      (node (ref "U3") (pin "23") (pinfunction "DVDD_23") (pintype "passive"))
      (node (ref "U3") (pin "30") (pinfunction "DVDD_30") (pintype "passive"))
      (node (ref "U3") (pin "41") (pinfunction "DVDD_41") (pintype "passive"))
    )
    (net (code "128") (name "Net-(J2-Pad9)") (class "Default")
      (node (ref "J2") (pin "9") (pinfunction "9_9") (pintype "passive"))
      (node (ref "R19") (pin "2") (pinfunction "2_2") (pintype "passive"))
    )
    (net (code "129") (name "Net-(J2-Pad12)") (class "Default")
      (node (ref "J2") (pin "12") (pinfunction "12_12") (pintype "passive"))
      (node (ref "R18") (pin "2") (pinfunction "2_2") (pintype "passive"))
    )
    (net (code "130") (name "Net-(U3-~{FDX{slash}COLLLED{slash}OP0})") (class "Default")
      (node (ref "R66") (pin "2") (pinfunction "2_2") (pintype "passive"))
      (node (ref "U3") (pin "11") (pinfunction "~{FDX/COLLLED/OP0}_11") (pintype "passive"))
    )
    (net (code "131") (name "Net-(Y1-EN{slash}D)") (class "Default")
      (node (ref "R24") (pin "1") (pinfunction "1_1") (pintype "passive"))
      (node (ref "Y1") (pin "1") (pinfunction "EN/D_1") (pintype "passive"))
    )
    (net (code "132") (name "Net-(Y1-OUTPUT)") (class "Default")
      (node (ref "R25") (pin "1") (pinfunction "1_1") (pintype "passive"))
      (node (ref "Y1") (pin "3") (pinfunction "OUTPUT_3") (pintype "power_in"))
    )
    (net (code "133") (name "unconnected-(J1-LE-Pad28)") (class "Default")
      (node (ref "J1") (pin "28") (pinfunction "LE_28") (pintype "passive+no_connect"))
    )
    (net (code "134") (name "unconnected-(J1-{slash}DF_CS-Pad30)") (class "Default")
      (node (ref "J1") (pin "30") (pinfunction "/DF_CS_30") (pintype "passive+no_connect"))
    )
    (net (code "135") (name "unconnected-(J1-{slash}SD_CS-Pad32)") (class "Default")
      (node (ref "J1") (pin "32") (pinfunction "/SD_CS_32") (pintype "passive+no_connect"))
    )
    (net (code "136") (name "unconnected-(J2-BI_D4+-Pad7)") (class "Default")
      (node (ref "J2") (pin "7") (pinfunction "BI_D4+_7") (pintype "passive+no_connect"))
    )
    (net (code "137") (name "unconnected-(J2-BI_D4--Pad8)") (class "Default")
      (node (ref "J2") (pin "8") (pinfunction "BI_D4-_8") (pintype "passive+no_connect"))
    )
    (net (code "138") (name "unconnected-(J2-Pad15)") (class "Default")
      (node (ref "J2") (pin "15") (pinfunction "15_15") (pintype "passive+no_connect"))
    )
    (net (code "139") (name "unconnected-(J2-Pad16)") (class "Default")
      (node (ref "J2") (pin "16") (pinfunction "16_16") (pintype "passive+no_connect"))
    )
    (net (code "140") (name "unconnected-(P1-NC-Pad18)") (class "Default")
      (node (ref "P1") (pin "18") (pinfunction "NC_18") (pintype "passive+no_connect"))
    )
    (net (code "141") (name "unconnected-(U3-BGRES-Pad48)") (class "Default")
      (node (ref "U3") (pin "48") (pinfunction "BGRES_48") (pintype "passive"))
    )
    (net (code "142") (name "unconnected-(U3-BGRESG-Pad47)") (class "Default")
      (node (ref "U3") (pin "47") (pinfunction "BGRESG_47") (pintype "passive"))
    )
    (net (code "143") (name "unconnected-(U3-CABLESTS{slash}LINKSTS-Pad14)") (class "Default")
      (node (ref "U3") (pin "14") (pinfunction "CABLESTS/LINKSTS_14") (pintype "passive+no_connect"))
    )
    (net (code "144") (name "unconnected-(U3-CRS{slash}PHYAD[4]-Pad35)") (class "Default")
      (node (ref "U3") (pin "35") (pinfunction "CRS/PHYAD[4]_35") (pintype "passive"))
    )
    (net (code "145") (name "unconnected-(U3-DISMDIX-Pad39)") (class "Default")
      (node (ref "U3") (pin "39") (pinfunction "DISMDIX_39") (pintype "passive"))
    )
    (net (code "146") (name "unconnected-(U3-NC-Pad45)") (class "Default")
      (node (ref "U3") (pin "45") (pinfunction "NC_45") (pintype "passive+no_connect"))
    )
    (net (code "147") (name "unconnected-(U3-RXCLK_{slash}10BTSER-Pad34)") (class "Default")
      (node (ref "U3") (pin "34") (pinfunction "RXCLK_/10BTSER_34") (pintype "passive"))
    )
    (net (code "148") (name "unconnected-(U3-RXD[2]{slash}PHYAD[2]-Pad27)") (class "Default")
      (node (ref "U3") (pin "27") (pinfunction "RXD[2]/PHYAD[2]_27") (pintype "passive"))
    )
    (net (code "149") (name "unconnected-(U3-RXD[3]{slash}PHYAD[3]-Pad26)") (class "Default")
      (node (ref "U3") (pin "26") (pinfunction "RXD[3]/PHYAD[3]_26") (pintype "passive"))
    )
    (net (code "150") (name "unconnected-(U3-RXER{slash}RXD[4]{slash}RPTR-Pad38)") (class "Default")
      (node (ref "U3") (pin "38") (pinfunction "RXER/RXD[4]/RPTR_38") (pintype "passive"))
    )
    (net (code "151") (name "unconnected-(U3-TXCLK{slash}ISOLATE-Pad22)") (class "Default")
      (node (ref "U3") (pin "22") (pinfunction "TXCLK/ISOLATE_22") (pintype "passive"))
    )
    (net (code "152") (name "unconnected-(U3-TXD[2]-Pad18)") (class "Default")
      (node (ref "U3") (pin "18") (pinfunction "TXD[2]_18") (pintype "passive"))
    )
    (net (code "153") (name "unconnected-(U3-TXD[3]-Pad17)") (class "Default")
      (node (ref "U3") (pin "17") (pinfunction "TXD[3]_17") (pintype "passive"))
    )
    (net (code "154") (name "unconnected-(U3-TXER{slash}TXD_[4]-Pad16)") (class "Default")
      (node (ref "U3") (pin "16") (pinfunction "TXER/TXD_[4]_16") (pintype "passive"))
    )
    (net (code "155") (name "unconnected-(U3-XT1-Pad43)") (class "Default")
      (node (ref "U3") (pin "43") (pinfunction "XT1_43") (pintype "passive+no_connect"))
    )
  )
)
